# blinker_board.net
KiCad netlist of a schematic drawn in EAGLE
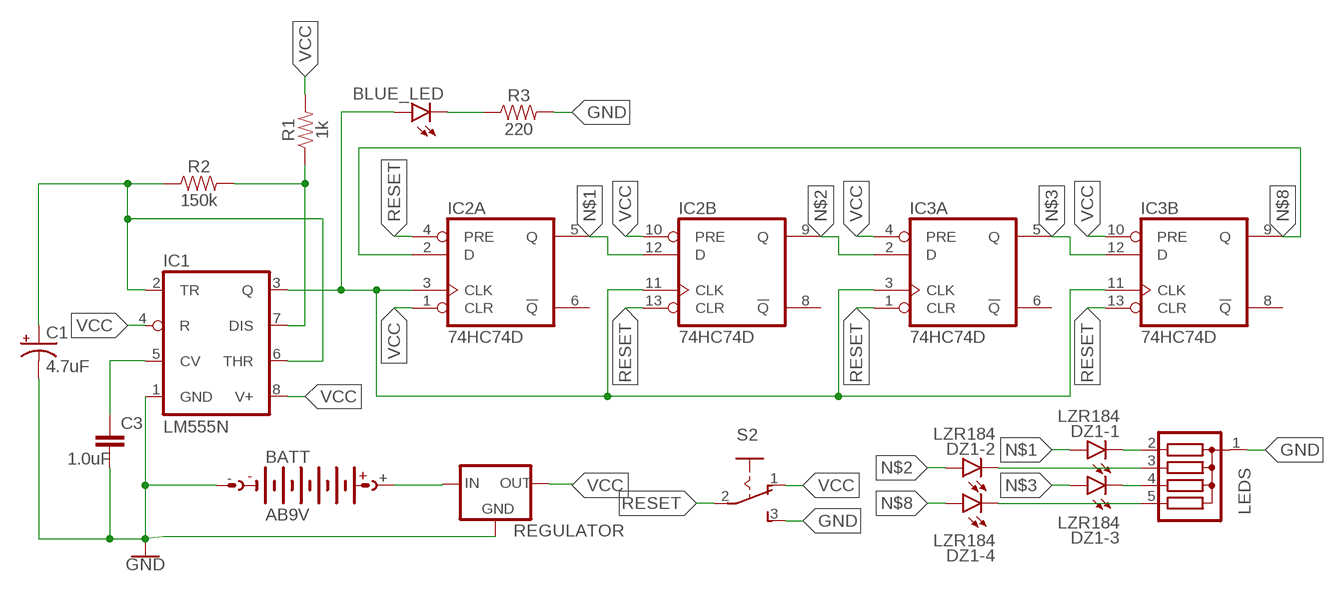
[diagram p0: schematic, sheet 1]

(export (version "E")
  (design (tool "Eeschema 10.0.6"))
  (components
    (comp (ref "BATT")
      (value "AB9V")
      (footprint "eagle-import:AB9V")
      (libsource (lib "eagle-import") (part "AB9V"))
    )
    (comp (ref "BLUE_LED")
      (value "LED")
      (footprint "eagle-import:SMARTLED-TTW")
      (libsource (lib "eagle-import") (part "LED"))
    )
    (comp (ref "C1")
      (value "4.7uF")
      (footprint "eagle-import:A_3216-18R")
      (libsource (lib "eagle-import") (part "CPOL-USA/3216-18R"))
    )
    (comp (ref "C3")
      (value "1.0uF")
      (footprint "eagle-import:0402")
      (libsource (lib "eagle-import") (part "1.0UF-0402-16V-10%"))
    )
    (comp (ref "DZ1")
      (value "LZR184")
      (footprint "eagle-import:LZR184")
      (libsource (lib "eagle-import") (part "LZR184"))
    )
    (comp (ref "IC1")
      (value "LM555N")
      (footprint "eagle-import:DIL08")
      (libsource (lib "eagle-import") (part "555NLM"))
    )
    (comp (ref "IC2")
      (value "74HC74D")
      (footprint "eagle-import:SO14")
      (libsource (lib "eagle-import") (part "7474DHC"))
    )
    (comp (ref "IC3")
      (value "74HC74D")
      (footprint "eagle-import:SO14")
      (libsource (lib "eagle-import") (part "7474DHC"))
    )
    (comp (ref "LEDS")
      (value "G04R")
      (footprint "eagle-import:SIL5")
      (libsource (lib "eagle-import") (part "G04R"))
    )
    (comp (ref "R1")
      (value "1k")
      (footprint "eagle-import:0603")
      (libsource (lib "eagle-import") (part "1KOHM-0603-1/10W-1%"))
    )
    (comp (ref "R2")
      (value "150k")
      (footprint "eagle-import:0603")
      (libsource (lib "eagle-import") (part "150KOHM-0603-1/10W-1%"))
    )
    (comp (ref "R3")
      (value "220")
      (footprint "eagle-import:0603")
      (libsource (lib "eagle-import") (part "220OHM-0603-1/10W-1%"))
    )
    (comp (ref "REGULATOR")
      (value "78MXXS")
      (footprint "eagle-import:78MXXS")
      (libsource (lib "eagle-import") (part "78MXXS"))
    )
    (comp (ref "S2")
      (value "255SB")
      (footprint "eagle-import:255SB")
      (libsource (lib "eagle-import") (part "255SB"))
    )
  )
  (nets
    (net (code "1") (name "GND") (class "Default")
      (node (ref "BATT") (pin "-") (pinfunction "-_-") (pintype "passive"))
      (node (ref "C1") (pin "-") (pinfunction "-_-") (pintype "passive"))
      (node (ref "C3") (pin "2") (pinfunction "2_2") (pintype "passive"))
      (node (ref "IC1") (pin "1") (pinfunction "GND_1") (pintype "power_in"))
      (node (ref "LEDS") (pin "1") (pinfunction "1_1") (pintype "passive"))
      (node (ref "R3") (pin "2") (pinfunction "2_2") (pintype "passive"))
      (node (ref "REGULATOR") (pin "GND") (pinfunction "GND_GND") (pintype "input"))
      (node (ref "S2") (pin "3") (pinfunction "S_3") (pintype "passive"))
    )
    (net (code "2") (name "N$1") (class "Default")
      (node (ref "DZ1") (pin "A1") (pinfunction "A_A1") (pintype "passive"))
      (node (ref "IC2") (pin "12") (pinfunction "D_12") (pintype "input"))
      (node (ref "IC2") (pin "5") (pinfunction "Q_5") (pintype "output"))
    )
    (net (code "3") (name "N$2") (class "Default")
      (node (ref "DZ1") (pin "A2") (pinfunction "A_A2") (pintype "passive"))
      (node (ref "IC2") (pin "9") (pinfunction "Q_9") (pintype "output"))
      (node (ref "IC3") (pin "2") (pinfunction "D_2") (pintype "input"))
    )
    (net (code "4") (name "N$3") (class "Default")
      (node (ref "DZ1") (pin "A3") (pinfunction "A_A3") (pintype "passive"))
      (node (ref "IC3") (pin "12") (pinfunction "D_12") (pintype "input"))
      (node (ref "IC3") (pin "5") (pinfunction "Q_5") (pintype "output"))
    )
    (net (code "5") (name "N$8") (class "Default")
      (node (ref "DZ1") (pin "A4") (pinfunction "A_A4") (pintype "passive"))
      (node (ref "IC2") (pin "2") (pinfunction "D_2") (pintype "input"))
      (node (ref "IC3") (pin "9") (pinfunction "Q_9") (pintype "output"))
    )
    (net (code "6") (name "Net-(BATT-Pad+)") (class "Default")
      (node (ref "BATT") (pin "+") (pinfunction "+_+") (pintype "passive"))
      (node (ref "REGULATOR") (pin "IN") (pinfunction "IN_IN") (pintype "input"))
    )
    (net (code "7") (name "Net-(BLUE_LED-A)") (class "Default")
      (node (ref "BLUE_LED") (pin "A@1") (pinfunction "A_A@1") (pintype "passive"))
      (node (ref "IC1") (pin "3") (pinfunction "Q_3") (pintype "output"))
      (node (ref "IC2") (pin "11") (pinfunction "CLK_11") (pintype "input"))
      (node (ref "IC2") (pin "3") (pinfunction "CLK_3") (pintype "input"))
      (node (ref "IC3") (pin "11") (pinfunction "CLK_11") (pintype "input"))
      (node (ref "IC3") (pin "3") (pinfunction "CLK_3") (pintype "input"))
    )
    (net (code "8") (name "Net-(BLUE_LED-C)") (class "Default")
      (node (ref "BLUE_LED") (pin "C@1") (pinfunction "C_C@1") (pintype "passive"))
      (node (ref "R3") (pin "1") (pinfunction "1_1") (pintype "passive"))
    )
    (net (code "9") (name "Net-(DZ1A-C)") (class "Default")
      (node (ref "DZ1") (pin "K1") (pinfunction "C_K1") (pintype "passive"))
      (node (ref "LEDS") (pin "2") (pinfunction "2_2") (pintype "passive"))
    )
    (net (code "10") (name "Net-(DZ1B-C)") (class "Default")
      (node (ref "DZ1") (pin "K2") (pinfunction "C_K2") (pintype "passive"))
      (node (ref "LEDS") (pin "3") (pinfunction "3_3") (pintype "passive"))
    )
    (net (code "11") (name "Net-(DZ1C-C)") (class "Default")
      (node (ref "DZ1") (pin "K3") (pinfunction "C_K3") (pintype "passive"))
      (node (ref "LEDS") (pin "4") (pinfunction "4_4") (pintype "passive"))
    )
    (net (code "12") (name "Net-(DZ1D-C)") (class "Default")
      (node (ref "DZ1") (pin "K4") (pinfunction "C_K4") (pintype "passive"))
      (node (ref "LEDS") (pin "5") (pinfunction "5_5") (pintype "passive"))
    )
    (net (code "13") (name "Net-(IC1-CV)") (class "Default")
      (node (ref "C3") (pin "1") (pinfunction "1_1") (pintype "passive"))
      (node (ref "IC1") (pin "5") (pinfunction "CV_5") (pintype "input"))
    )
    (net (code "14") (name "Net-(IC1-DIS)") (class "Default")
      (node (ref "IC1") (pin "7") (pinfunction "DIS_7") (pintype "input"))
      (node (ref "R1") (pin "1") (pinfunction "1_1") (pintype "passive"))
      (node (ref "R2") (pin "2") (pinfunction "2_2") (pintype "passive"))
    )
    (net (code "15") (name "Net-(IC1-THR)") (class "Default")
      (node (ref "C1") (pin "+") (pinfunction "+_+") (pintype "passive"))
      (node (ref "IC1") (pin "2") (pinfunction "TR_2") (pintype "input"))
      (node (ref "IC1") (pin "6") (pinfunction "THR_6") (pintype "input"))
      (node (ref "R2") (pin "1") (pinfunction "1_1") (pintype "passive"))
    )
    (net (code "16") (name "RESET") (class "Default")
      (node (ref "IC2") (pin "13") (pinfunction "CLR_13") (pintype "input"))
      (node (ref "IC2") (pin "4") (pinfunction "PRE_4") (pintype "input"))
      (node (ref "IC3") (pin "1") (pinfunction "CLR_1") (pintype "input"))
      (node (ref "IC3") (pin "13") (pinfunction "CLR_13") (pintype "input"))
      (node (ref "S2") (pin "2") (pinfunction "P_2") (pintype "passive"))
    )
    (net (code "17") (name "VCC") (class "Default")
      (node (ref "IC1") (pin "4") (pinfunction "R_4") (pintype "input"))
      (node (ref "IC1") (pin "8") (pinfunction "V+_8") (pintype "power_in"))
      (node (ref "IC2") (pin "1") (pinfunction "CLR_1") (pintype "input"))
      (node (ref "IC2") (pin "10") (pinfunction "PRE_10") (pintype "input"))
      (node (ref "IC3") (pin "10") (pinfunction "PRE_10") (pintype "input"))
      (node (ref "IC3") (pin "4") (pinfunction "PRE_4") (pintype "input"))
      (node (ref "R1") (pin "2") (pinfunction "2_2") (pintype "passive"))
      (node (ref "REGULATOR") (pin "OUT") (pinfunction "OUT_OUT") (pintype "passive"))
      (node (ref "S2") (pin "1") (pinfunction "O_1") (pintype "passive"))
    )
    (net (code "18") (name "unconnected-(IC2A-~{Q}-Pad6)") (class "Default")
      (node (ref "IC2") (pin "6") (pinfunction "~{Q}_6") (pintype "output"))
    )
    (net (code "19") (name "unconnected-(IC2B-~{Q}-Pad8)") (class "Default")
      (node (ref "IC2") (pin "8") (pinfunction "~{Q}_8") (pintype "output"))
    )
    (net (code "20") (name "unconnected-(IC3A-~{Q}-Pad6)") (class "Default")
      (node (ref "IC3") (pin "6") (pinfunction "~{Q}_6") (pintype "output"))
    )
    (net (code "21") (name "unconnected-(IC3B-~{Q}-Pad8)") (class "Default")
      (node (ref "IC3") (pin "8") (pinfunction "~{Q}_8") (pintype "output"))
    )
  )
)
